# Grove_-_3-Axis_Digital_Gyro_v1_2.net
KiCad netlist of a schematic drawn in EAGLE
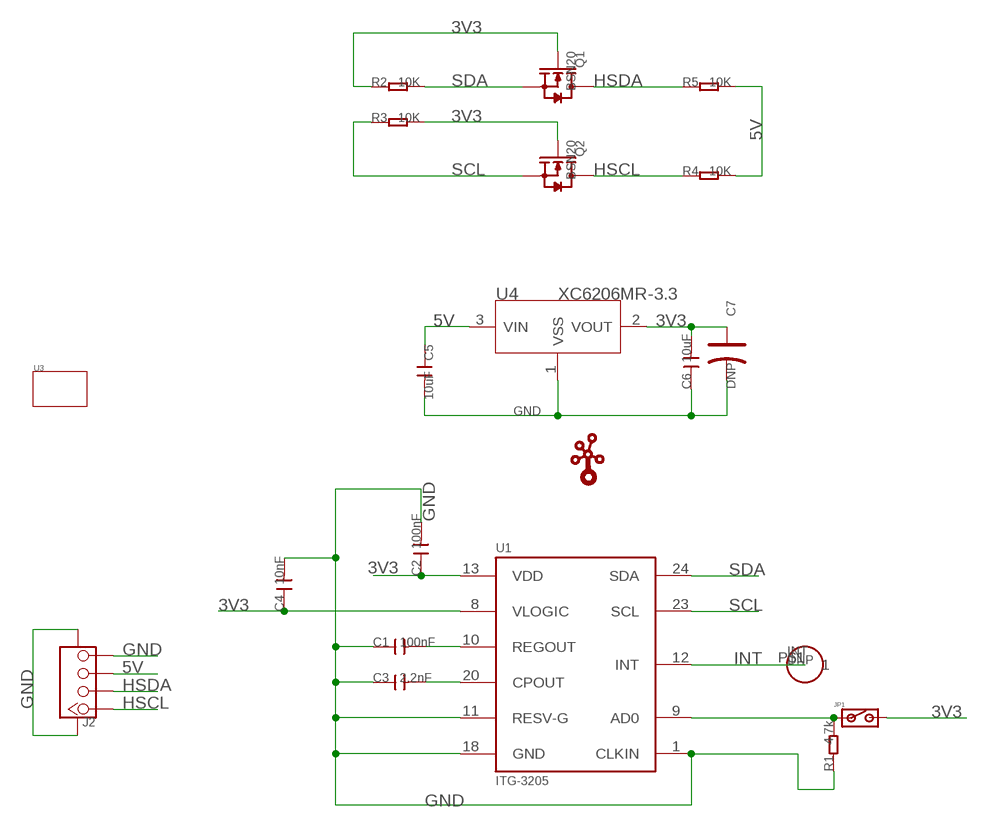
[diagram p0: schematic, sheet 1]

(export (version "E")
  (design (tool "Eeschema 10.0.6"))
  (components
    (comp (ref "C1")
      (value "100nF")
      (footprint "eagle-import:C0603")
      (libsource (lib "eagle-import") (part "C-0603"))
    )
    (comp (ref "C2")
      (value "100nF")
      (footprint "eagle-import:C0603")
      (libsource (lib "eagle-import") (part "C-0603"))
    )
    (comp (ref "C3")
      (value "2.2nF")
      (footprint "eagle-import:C0603")
      (libsource (lib "eagle-import") (part "C-0603"))
    )
    (comp (ref "C4")
      (value "10nF")
      (footprint "eagle-import:C0603")
      (libsource (lib "eagle-import") (part "C-0603"))
    )
    (comp (ref "C5")
      (value "10uF")
      (footprint "eagle-import:C0805")
      (libsource (lib "eagle-import") (part "C-0805"))
    )
    (comp (ref "C6")
      (value "10uF")
      (footprint "eagle-import:C0805")
      (libsource (lib "eagle-import") (part "C-0805"))
    )
    (comp (ref "C7")
      (value "DNP")
      (footprint "eagle-import:AVX-A")
      (libsource (lib "eagle-import") (part "CAP-AVX-A"))
    )
    (comp (ref "INT")
      (value "DNP")
      (footprint "eagle-import:CK_1X1")
      (libsource (lib "eagle-import") (part "CK_1X132"))
    )
    (comp (ref "J2")
      (value "TWIG-4P-2.0-SMD-FEMALE-REINFORCE'DD'")
      (footprint "eagle-import:4P-SMD-2.0")
      (libsource (lib "eagle-import") (part "TWIG-4P-2.0-SMD-FEMALE-REINFORCE'DD'"))
    )
    (comp (ref "JP1")
      (value "DNP")
      (footprint "eagle-import:JP_SW")
      (libsource (lib "eagle-import") (part "JP_SW"))
    )
    (comp (ref "Q1")
      (value "BSN20")
      (footprint "eagle-import:SOT23")
      (libsource (lib "eagle-import") (part "MOSFET-N'SOT23'"))
    )
    (comp (ref "Q2")
      (value "BSN20")
      (footprint "eagle-import:SOT23")
      (libsource (lib "eagle-import") (part "MOSFET-N'SOT23'"))
    )
    (comp (ref "R1")
      (value "4.7k")
      (footprint "eagle-import:R0603")
      (libsource (lib "eagle-import") (part "R-0603"))
    )
    (comp (ref "R2")
      (value "10K")
      (footprint "eagle-import:R0603")
      (libsource (lib "eagle-import") (part "R-0603"))
    )
    (comp (ref "R3")
      (value "10K")
      (footprint "eagle-import:R0603")
      (libsource (lib "eagle-import") (part "R-0603"))
    )
    (comp (ref "R4")
      (value "10K")
      (footprint "eagle-import:R0603")
      (libsource (lib "eagle-import") (part "R-0603"))
    )
    (comp (ref "R5")
      (value "10K")
      (footprint "eagle-import:R0603")
      (libsource (lib "eagle-import") (part "R-0603"))
    )
    (comp (ref "U$1")
      (value "TWIGLOGOTWIGLOGO_SMALL")
      (footprint "eagle-import:TWIGLOGO_SMALL")
      (libsource (lib "eagle-import") (part "TWIGLOGOTWIGLOGO_SMALL"))
    )
    (comp (ref "U1")
      (value "ITG-3205")
      (footprint "eagle-import:QFN-24")
      (libsource (lib "eagle-import") (part "ITG-3200"))
    )
    (comp (ref "U3")
      (value "TWIG'1U'")
      (footprint "eagle-import:1U-DIM-W_-DRILL")
      (libsource (lib "eagle-import") (part "TWIG'1U'"))
    )
    (comp (ref "U4")
      (value "XC6206MR-3.3")
      (footprint "eagle-import:SOT23")
      (libsource (lib "eagle-import") (part "XC6206MR"))
    )
  )
  (nets
    (net (code "1") (name "/3V3") (class "Default")
      (node (ref "C2") (pin "1") (pinfunction "1_1") (pintype "passive"))
      (node (ref "C4") (pin "1") (pinfunction "1_1") (pintype "passive"))
      (node (ref "C6") (pin "2") (pinfunction "2_2") (pintype "passive"))
      (node (ref "C7") (pin "+") (pinfunction "+_+") (pintype "passive"))
      (node (ref "JP1") (pin "2") (pinfunction "2_2") (pintype "bidirectional"))
      (node (ref "Q1") (pin "1") (pinfunction "G_1") (pintype "passive"))
      (node (ref "Q2") (pin "1") (pinfunction "G_1") (pintype "passive"))
      (node (ref "R2") (pin "1") (pinfunction "1_1") (pintype "passive"))
      (node (ref "R3") (pin "2") (pinfunction "2_2") (pintype "passive"))
      (node (ref "U1") (pin "13") (pinfunction "VDD_13") (pintype "bidirectional"))
      (node (ref "U1") (pin "8") (pinfunction "VLOGIC_8") (pintype "bidirectional"))
      (node (ref "U4") (pin "2") (pinfunction "VOUT_2") (pintype "output"))
    )
    (net (code "2") (name "/5V") (class "Default")
      (node (ref "C5") (pin "1") (pinfunction "1_1") (pintype "passive"))
      (node (ref "J2") (pin "3") (pinfunction "3_3") (pintype "bidirectional"))
      (node (ref "R4") (pin "2") (pinfunction "2_2") (pintype "passive"))
      (node (ref "R5") (pin "2") (pinfunction "2_2") (pintype "passive"))
      (node (ref "U4") (pin "3") (pinfunction "VIN_3") (pintype "input"))
    )
    (net (code "3") (name "/GND") (class "Default")
      (node (ref "C1") (pin "1") (pinfunction "1_1") (pintype "passive"))
      (node (ref "C2") (pin "2") (pinfunction "2_2") (pintype "passive"))
      (node (ref "C3") (pin "1") (pinfunction "1_1") (pintype "passive"))
      (node (ref "C4") (pin "2") (pinfunction "2_2") (pintype "passive"))
      (node (ref "C5") (pin "2") (pinfunction "2_2") (pintype "passive"))
      (node (ref "C6") (pin "1") (pinfunction "1_1") (pintype "passive"))
      (node (ref "C7") (pin "-") (pinfunction "-_-") (pintype "passive"))
      (node (ref "J2") (pin "4") (pinfunction "4_4") (pintype "bidirectional"))
      (node (ref "J2") (pin "SS1") (pinfunction "SS1_SS1") (pintype "bidirectional"))
      (node (ref "J2") (pin "SS2") (pinfunction "SS2_SS2") (pintype "bidirectional"))
      (node (ref "R1") (pin "1") (pinfunction "1_1") (pintype "passive"))
      (node (ref "U1") (pin "1") (pinfunction "CLKIN_1") (pintype "bidirectional"))
      (node (ref "U1") (pin "11") (pinfunction "RESV-G_11") (pintype "bidirectional"))
      (node (ref "U1") (pin "18") (pinfunction "GND_18") (pintype "bidirectional"))
      (node (ref "U4") (pin "1") (pinfunction "VSS_1") (pintype "power_in"))
    )
    (net (code "4") (name "/HSCL") (class "Default")
      (node (ref "J2") (pin "1") (pinfunction "1_1") (pintype "bidirectional"))
      (node (ref "Q2") (pin "3") (pinfunction "D_3") (pintype "passive"))
      (node (ref "R4") (pin "1") (pinfunction "1_1") (pintype "passive"))
    )
    (net (code "5") (name "/HSDA") (class "Default")
      (node (ref "J2") (pin "2") (pinfunction "2_2") (pintype "bidirectional"))
      (node (ref "Q1") (pin "3") (pinfunction "D_3") (pintype "passive"))
      (node (ref "R5") (pin "1") (pinfunction "1_1") (pintype "passive"))
    )
    (net (code "6") (name "/INT") (class "Default")
      (node (ref "INT") (pin "P$1") (pinfunction "1_P$1") (pintype "bidirectional"))
      (node (ref "U1") (pin "12") (pinfunction "INT_12") (pintype "bidirectional"))
    )
    (net (code "7") (name "/SCL") (class "Default")
      (node (ref "Q2") (pin "2") (pinfunction "S_2") (pintype "passive"))
      (node (ref "R3") (pin "1") (pinfunction "1_1") (pintype "passive"))
      (node (ref "U1") (pin "23") (pinfunction "SCL_23") (pintype "bidirectional"))
    )
    (net (code "8") (name "/SDA") (class "Default")
      (node (ref "Q1") (pin "2") (pinfunction "S_2") (pintype "passive"))
      (node (ref "R2") (pin "2") (pinfunction "2_2") (pintype "passive"))
      (node (ref "U1") (pin "24") (pinfunction "SDA_24") (pintype "bidirectional"))
    )
    (net (code "9") (name "Net-(U1-AD0)") (class "Default")
      (node (ref "JP1") (pin "1") (pinfunction "1_1") (pintype "bidirectional"))
      (node (ref "R1") (pin "2") (pinfunction "2_2") (pintype "passive"))
      (node (ref "U1") (pin "9") (pinfunction "AD0_9") (pintype "bidirectional"))
    )
    (net (code "10") (name "Net-(U1-CPOUT)") (class "Default")
      (node (ref "C3") (pin "2") (pinfunction "2_2") (pintype "passive"))
      (node (ref "U1") (pin "20") (pinfunction "CPOUT_20") (pintype "bidirectional"))
    )
    (net (code "11") (name "Net-(U1-REGOUT)") (class "Default")
      (node (ref "C1") (pin "2") (pinfunction "2_2") (pintype "passive"))
      (node (ref "U1") (pin "10") (pinfunction "REGOUT_10") (pintype "bidirectional"))
    )
  )
)
